# WSC2022SE_TP16_MA2_SPDIF_StartingPoint__.net
KiCad netlist of a schematic drawn in EAGLE
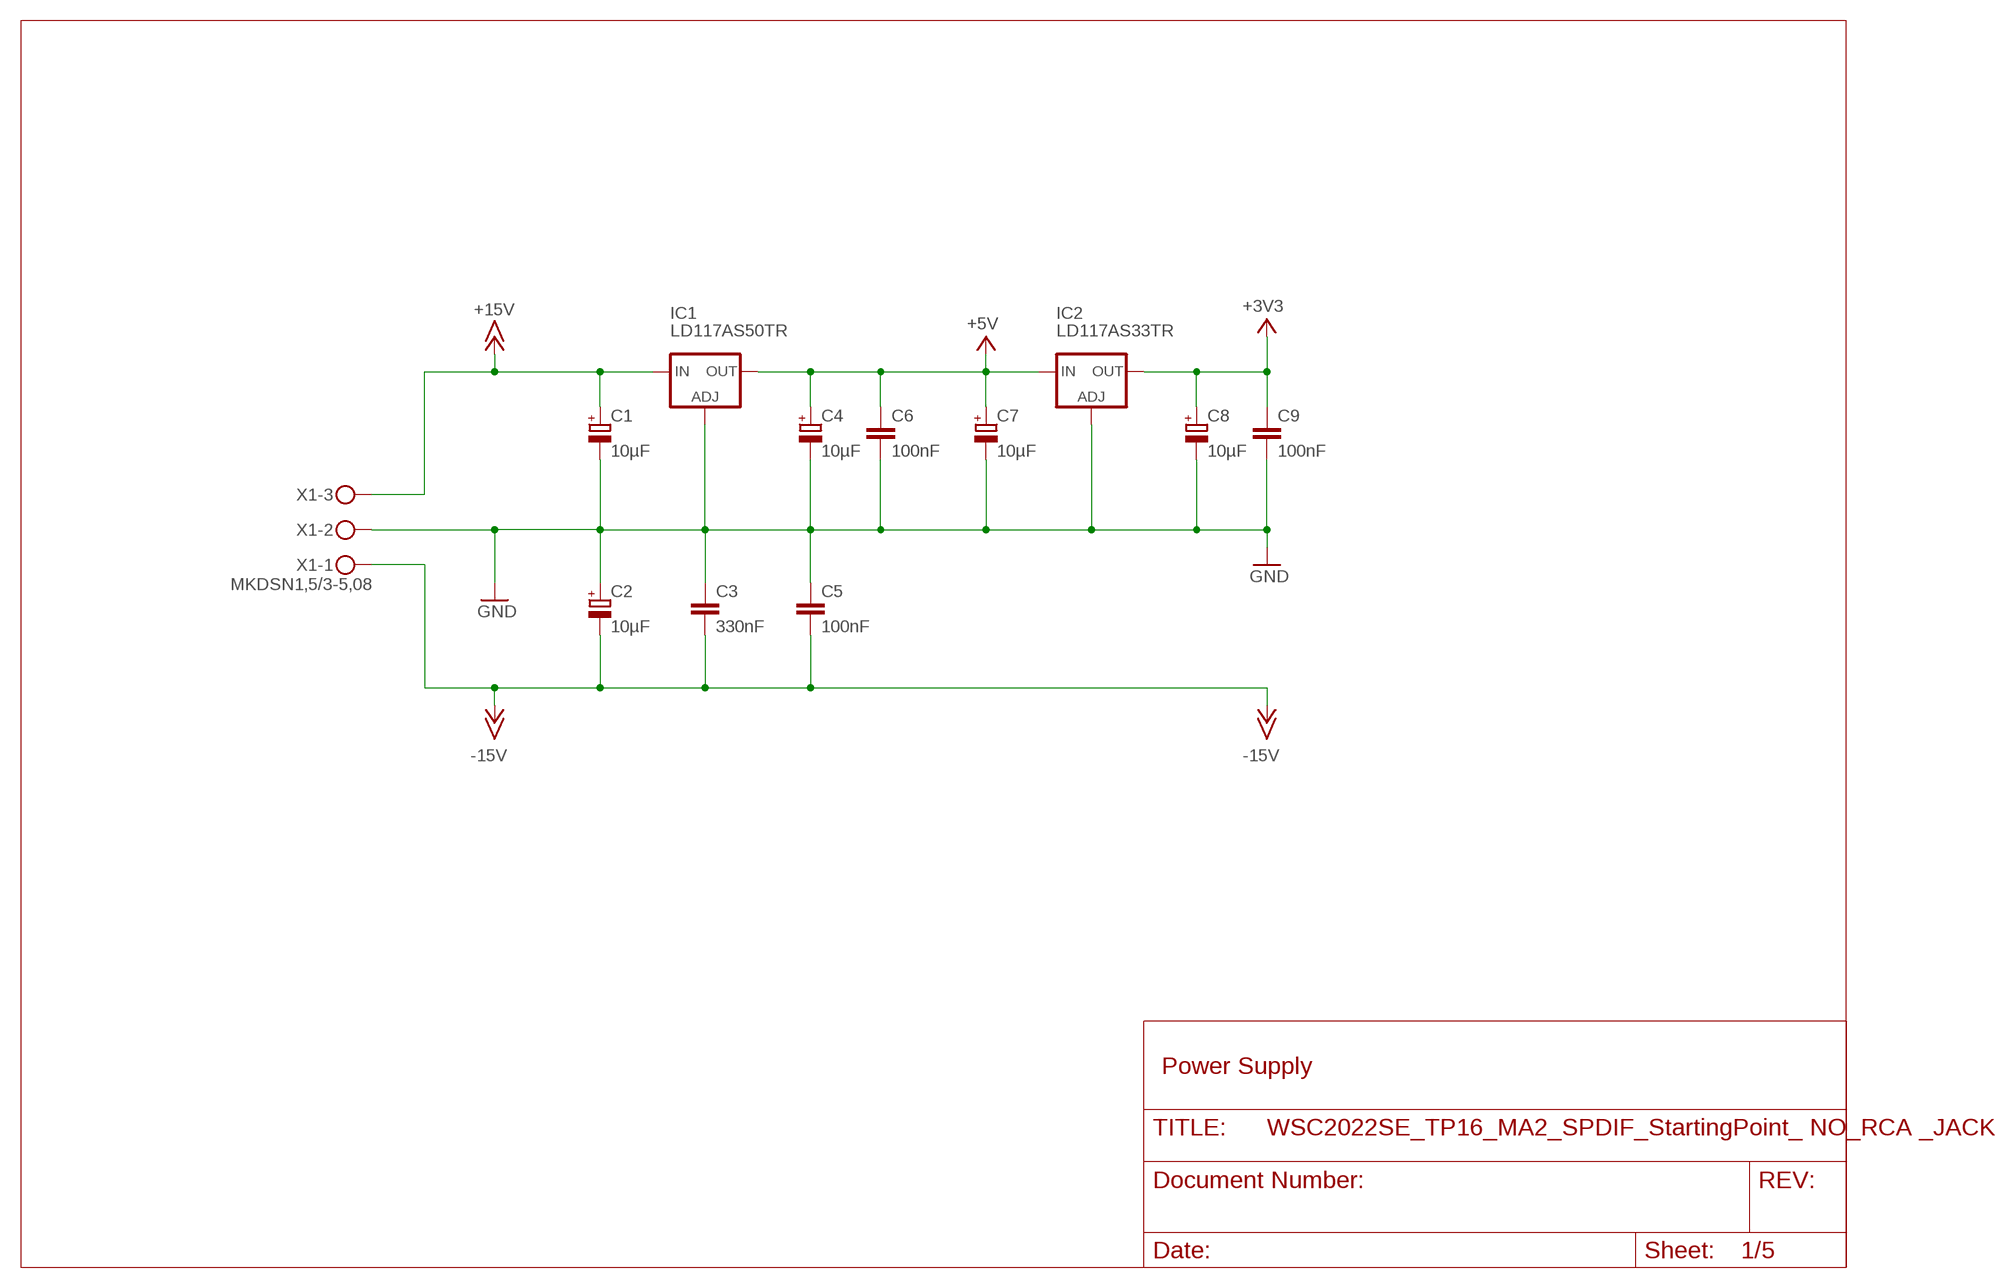
[diagram p0: schematic, sheet 1]
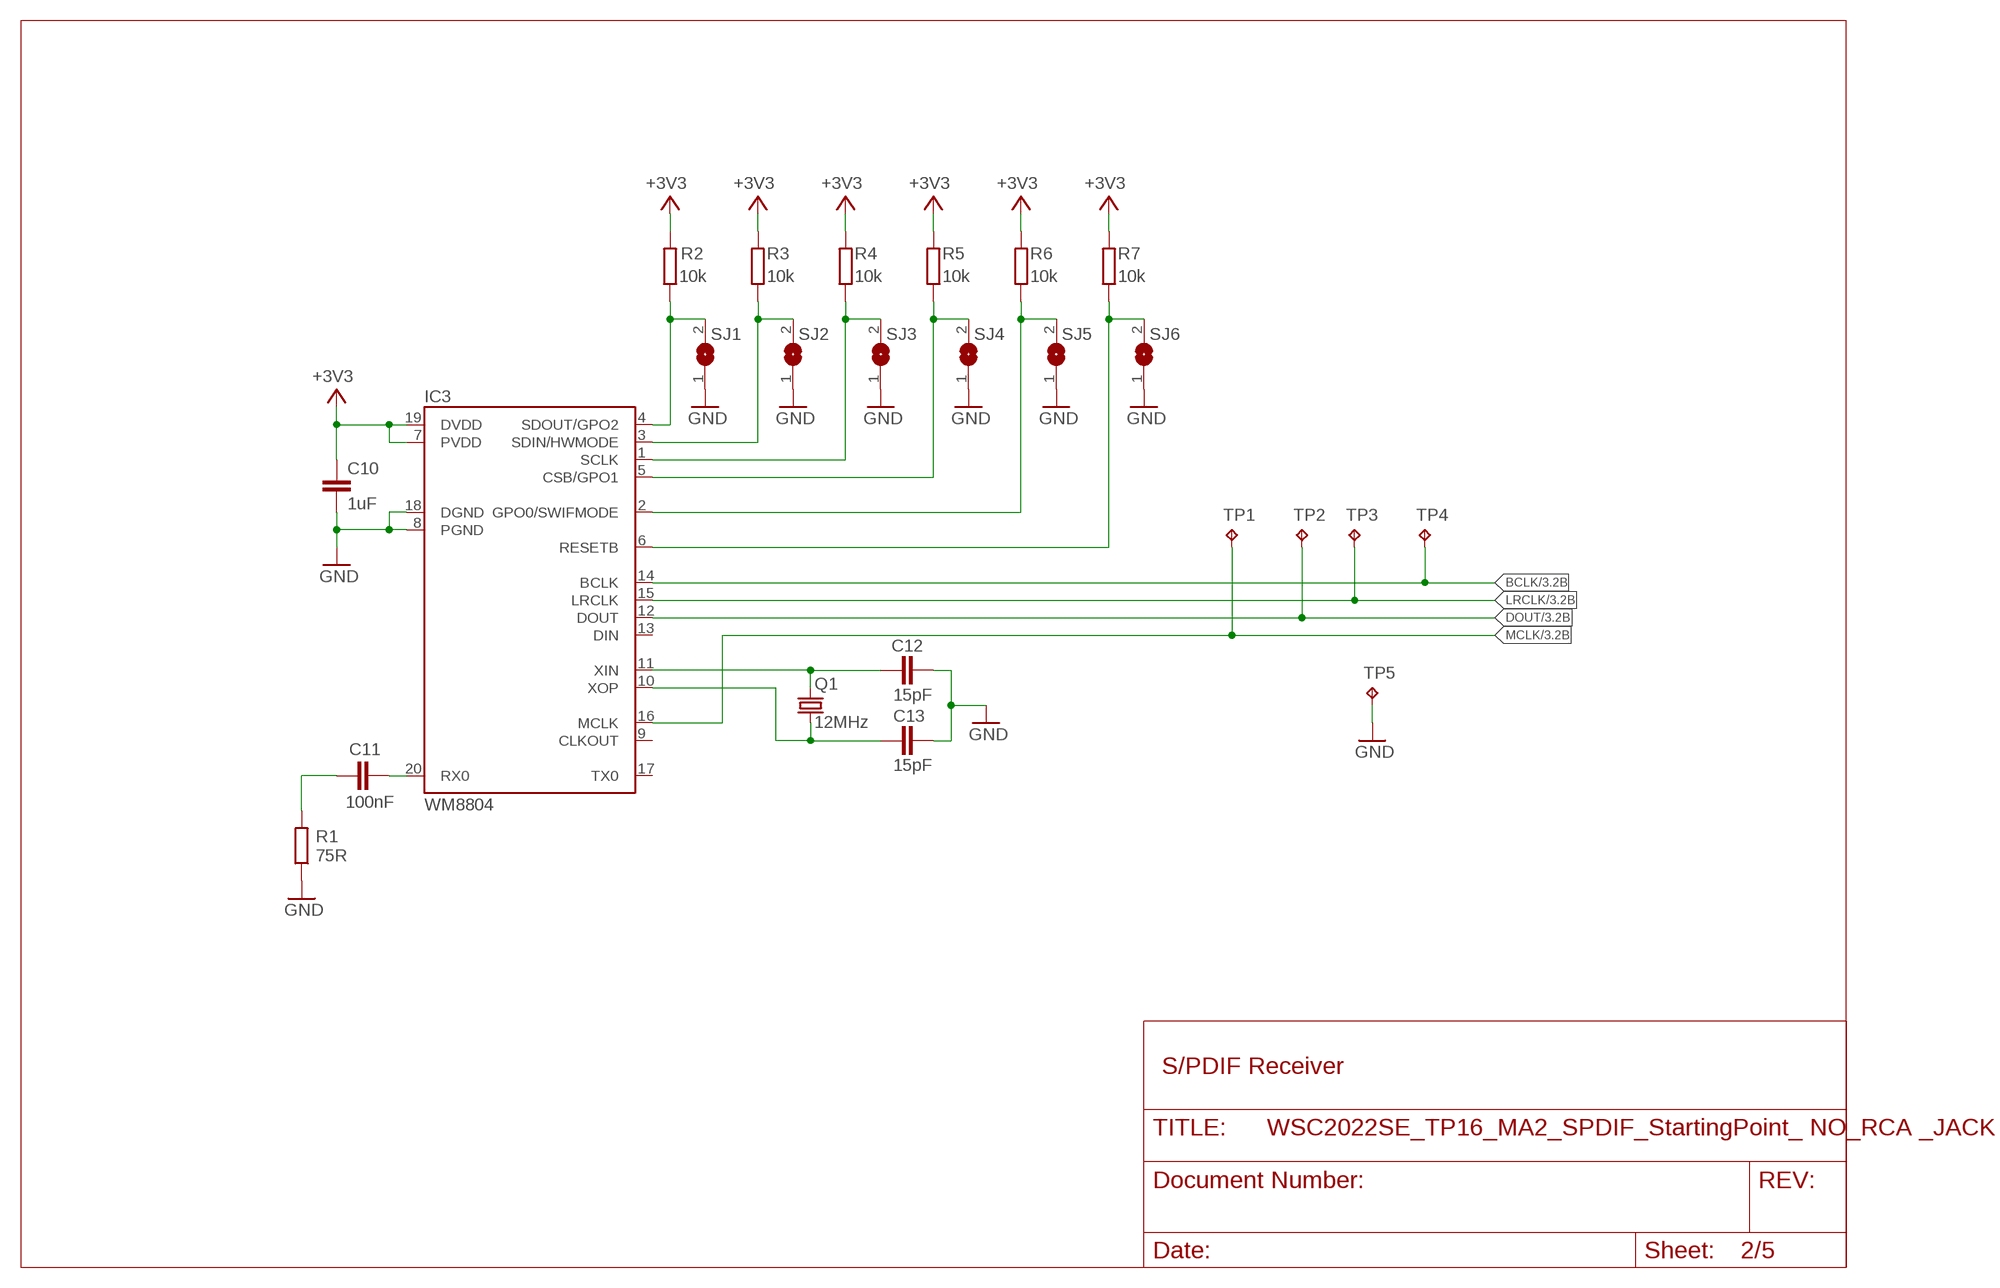
[diagram p1: schematic, sheet 2]
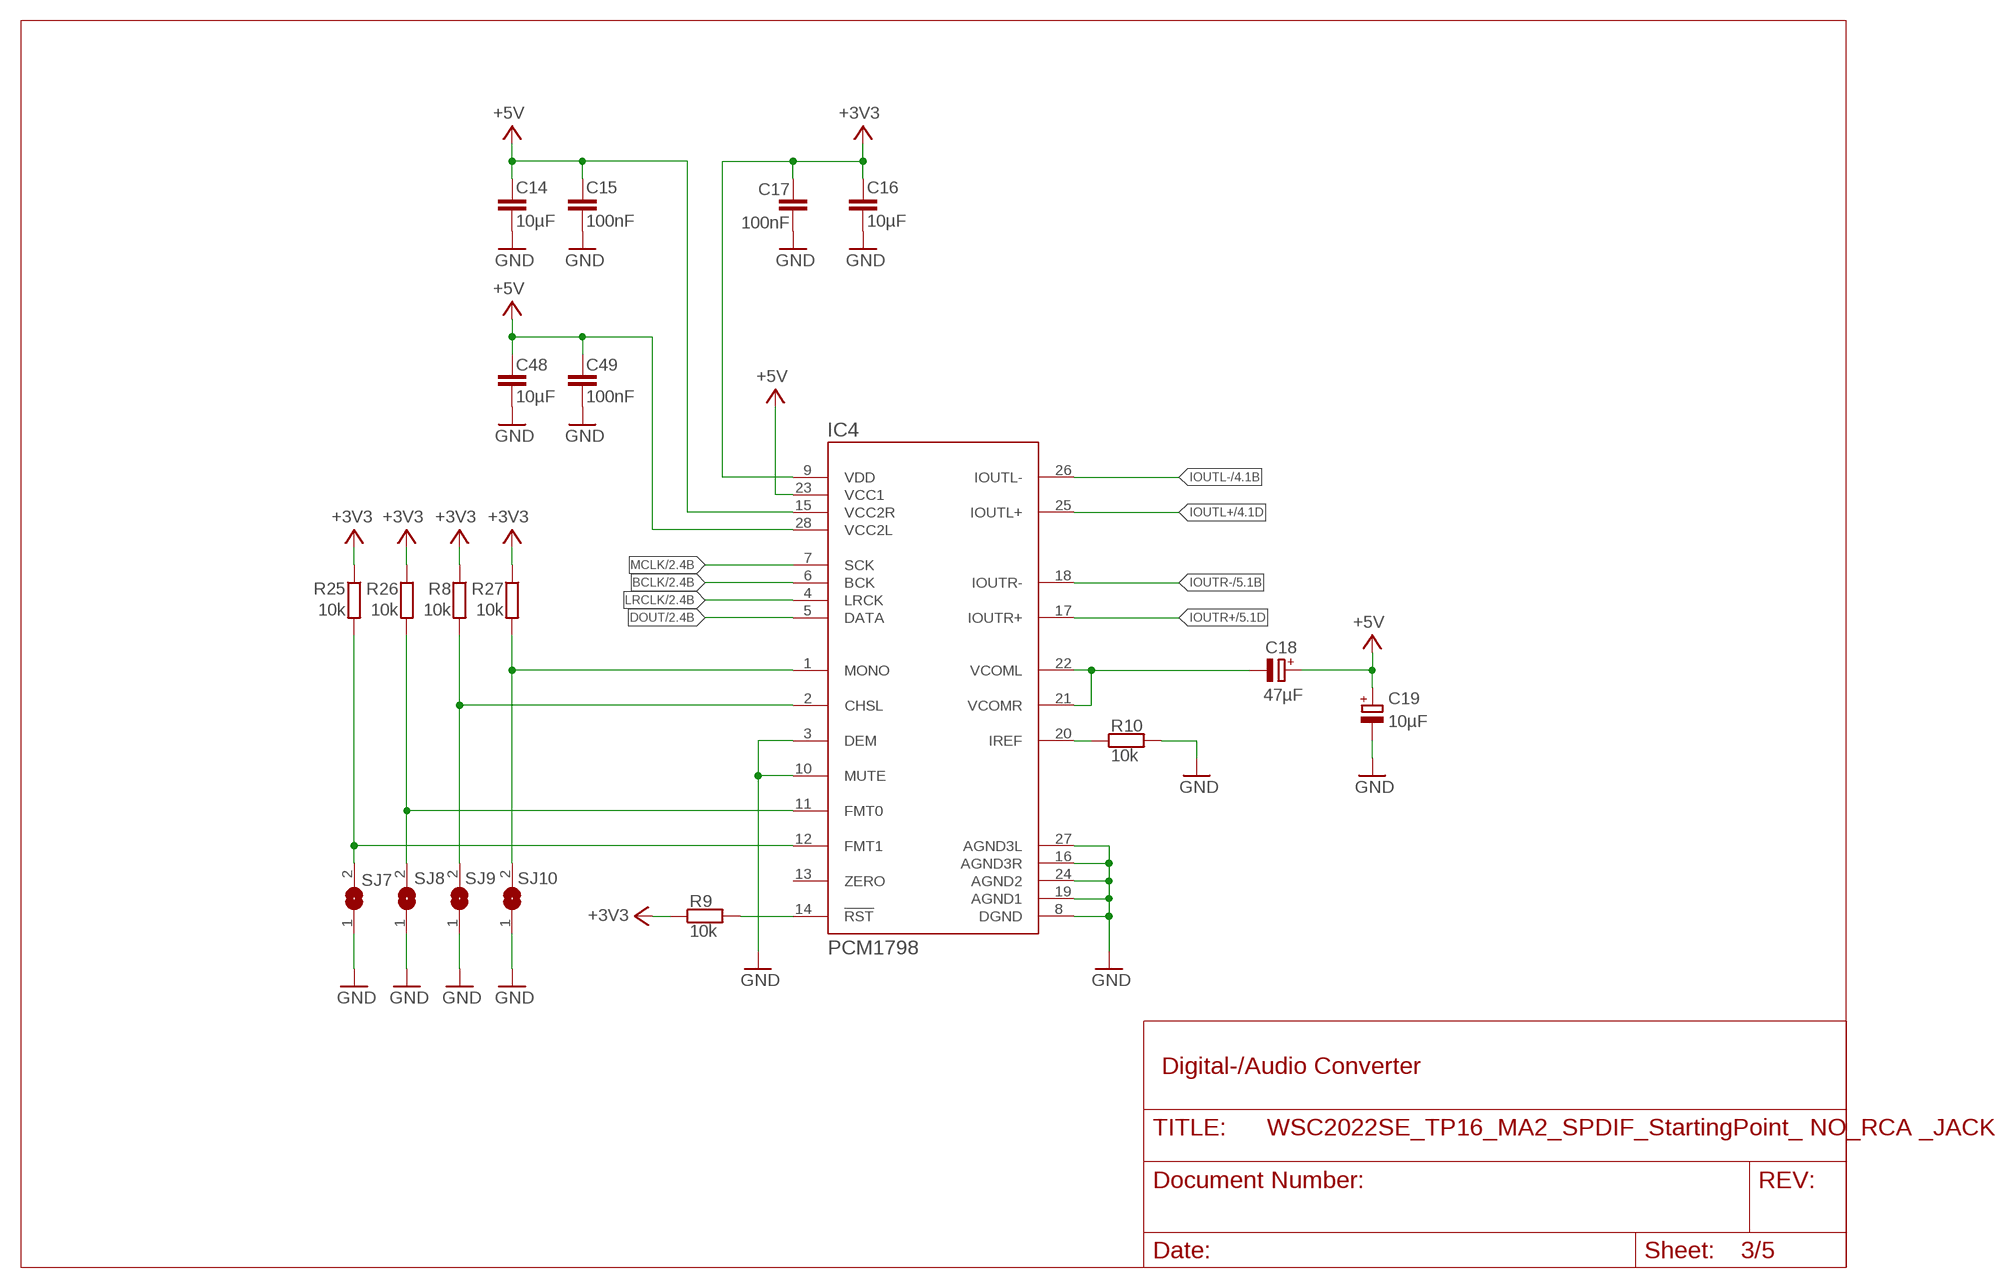
[diagram p2: schematic, sheet 3]
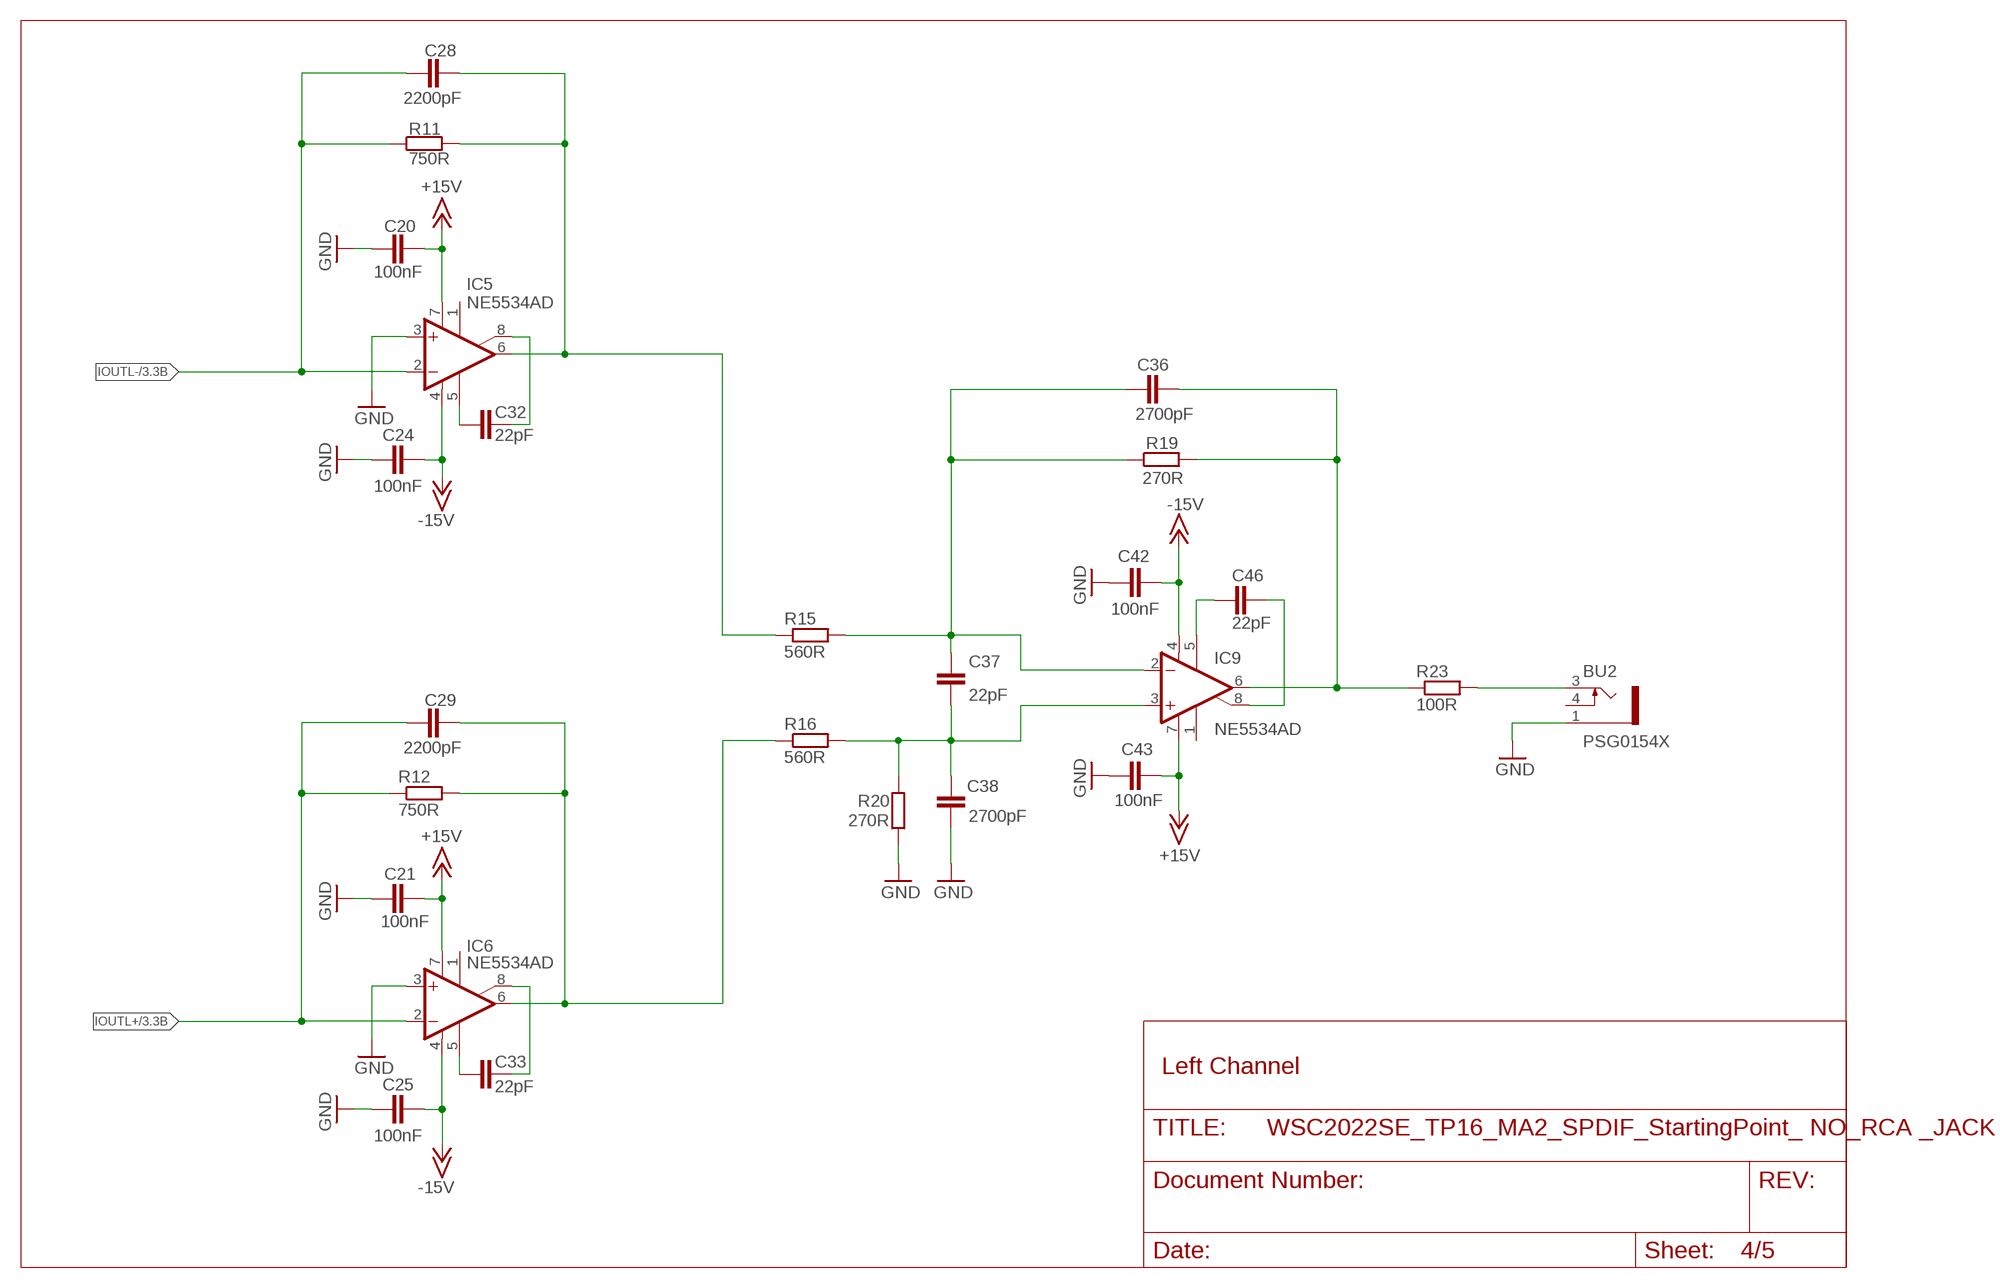
[diagram p3: schematic, sheet 4]
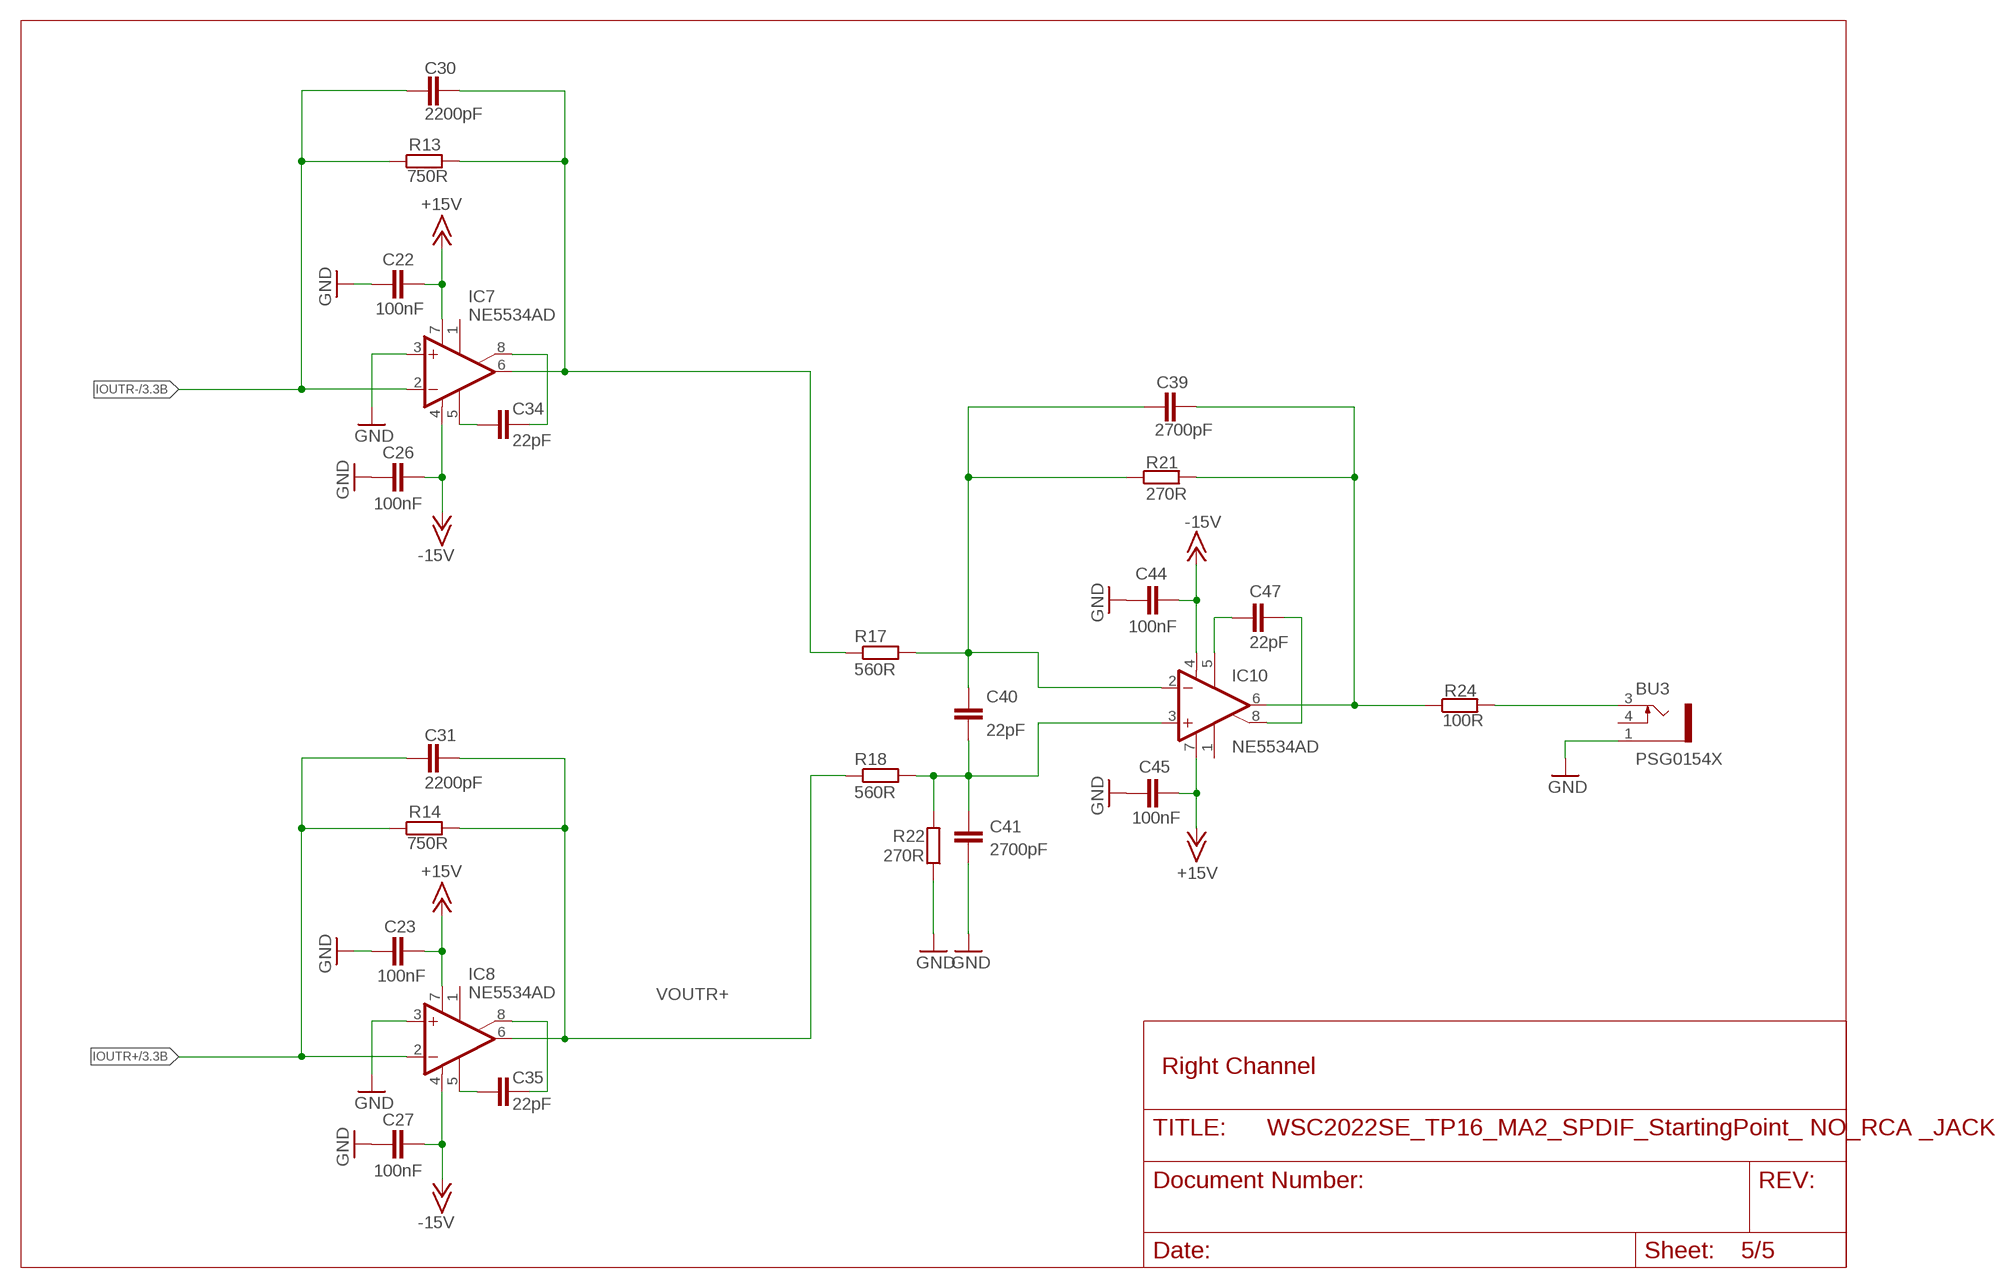
[diagram p4: schematic, sheet 5]

(export (version "E")
  (design (tool "Eeschema 10.0.6"))
  (components
    (comp (ref "BU2")
      (value "PSG0154X")
      (footprint "eagle-import:PHONO-3P")
      (libsource (lib "eagle-import") (part "PSG0154X"))
    )
    (comp (ref "C20")
      (value "100nF")
      (footprint "eagle-import:C0805")
      (libsource (lib "eagle-import") (part "C-EUC0805"))
    )
    (comp (ref "C21")
      (value "100nF")
      (footprint "eagle-import:C0805")
      (libsource (lib "eagle-import") (part "C-EUC0805"))
    )
    (comp (ref "C24")
      (value "100nF")
      (footprint "eagle-import:C0805")
      (libsource (lib "eagle-import") (part "C-EUC0805"))
    )
    (comp (ref "C25")
      (value "100nF")
      (footprint "eagle-import:C0805")
      (libsource (lib "eagle-import") (part "C-EUC0805"))
    )
    (comp (ref "C28")
      (value "2200pF")
      (footprint "eagle-import:C0805")
      (libsource (lib "eagle-import") (part "C-EUC0805"))
    )
    (comp (ref "C29")
      (value "2200pF")
      (footprint "eagle-import:C0805")
      (libsource (lib "eagle-import") (part "C-EUC0805"))
    )
    (comp (ref "C32")
      (value "22pF")
      (footprint "eagle-import:C0805")
      (libsource (lib "eagle-import") (part "C-EUC0805"))
    )
    (comp (ref "C33")
      (value "22pF")
      (footprint "eagle-import:C0805")
      (libsource (lib "eagle-import") (part "C-EUC0805"))
    )
    (comp (ref "C36")
      (value "2700pF")
      (footprint "eagle-import:C0805")
      (libsource (lib "eagle-import") (part "C-EUC0805"))
    )
    (comp (ref "C37")
      (value "22pF")
      (footprint "eagle-import:C0805")
      (libsource (lib "eagle-import") (part "C-EUC0805"))
    )
    (comp (ref "C38")
      (value "2700pF")
      (footprint "eagle-import:C0805")
      (libsource (lib "eagle-import") (part "C-EUC0805"))
    )
    (comp (ref "C42")
      (value "100nF")
      (footprint "eagle-import:C0805")
      (libsource (lib "eagle-import") (part "C-EUC0805"))
    )
    (comp (ref "C43")
      (value "100nF")
      (footprint "eagle-import:C0805")
      (libsource (lib "eagle-import") (part "C-EUC0805"))
    )
    (comp (ref "C46")
      (value "22pF")
      (footprint "eagle-import:C0805")
      (libsource (lib "eagle-import") (part "C-EUC0805"))
    )
    (comp (ref "IC5")
      (value "NE5534AD")
      (footprint "eagle-import:SO08")
      (libsource (lib "eagle-import") (part "NE5534DA"))
    )
    (comp (ref "IC6")
      (value "NE5534AD")
      (footprint "eagle-import:SO08")
      (libsource (lib "eagle-import") (part "NE5534DA"))
    )
    (comp (ref "IC9")
      (value "NE5534AD")
      (footprint "eagle-import:SO08")
      (libsource (lib "eagle-import") (part "NE5534DA"))
    )
    (comp (ref "R11")
      (value "750R")
      (footprint "eagle-import:R0805")
      (libsource (lib "eagle-import") (part "R-EU_R0805"))
    )
    (comp (ref "R12")
      (value "750R")
      (footprint "eagle-import:R0805")
      (libsource (lib "eagle-import") (part "R-EU_R0805"))
    )
    (comp (ref "R15")
      (value "560R")
      (footprint "eagle-import:R0805")
      (libsource (lib "eagle-import") (part "R-EU_R0805"))
    )
    (comp (ref "R16")
      (value "560R")
      (footprint "eagle-import:R0805")
      (libsource (lib "eagle-import") (part "R-EU_R0805"))
    )
    (comp (ref "R19")
      (value "270R")
      (footprint "eagle-import:R0805")
      (libsource (lib "eagle-import") (part "R-EU_R0805"))
    )
    (comp (ref "R20")
      (value "270R")
      (footprint "eagle-import:R0805")
      (libsource (lib "eagle-import") (part "R-EU_R0805"))
    )
    (comp (ref "R23")
      (value "100R")
      (footprint "eagle-import:R0805")
      (libsource (lib "eagle-import") (part "R-EU_R0805"))
    )
    (comp (ref "C14")
      (value "10µF")
      (footprint "eagle-import:C0805")
      (libsource (lib "eagle-import") (part "C-EUC0805"))
    )
    (comp (ref "C15")
      (value "100nF")
      (footprint "eagle-import:C0805")
      (libsource (lib "eagle-import") (part "C-EUC0805"))
    )
    (comp (ref "C16")
      (value "10µF")
      (footprint "eagle-import:C0805")
      (libsource (lib "eagle-import") (part "C-EUC0805"))
    )
    (comp (ref "C17")
      (value "100nF")
      (footprint "eagle-import:C0805")
      (libsource (lib "eagle-import") (part "C-EUC0805"))
    )
    (comp (ref "C18")
      (value "47µF")
      (footprint "eagle-import:PANASONIC_C")
      (libsource (lib "eagle-import") (part "CPOL-EUC"))
    )
    (comp (ref "C19")
      (value "10µF")
      (footprint "eagle-import:PANASONIC_B")
      (libsource (lib "eagle-import") (part "CPOL-EUB"))
    )
    (comp (ref "C48")
      (value "10µF")
      (footprint "eagle-import:C0805")
      (libsource (lib "eagle-import") (part "C-EUC0805"))
    )
    (comp (ref "C49")
      (value "100nF")
      (footprint "eagle-import:C0805")
      (libsource (lib "eagle-import") (part "C-EUC0805"))
    )
    (comp (ref "IC4")
      (value "PCM1798")
      (footprint "eagle-import:SSOP28")
      (libsource (lib "eagle-import") (part "PCM1798"))
    )
    (comp (ref "R8")
      (value "10k")
      (footprint "eagle-import:R0805")
      (libsource (lib "eagle-import") (part "R-EU_R0805"))
    )
    (comp (ref "R9")
      (value "10k")
      (footprint "eagle-import:R0805")
      (libsource (lib "eagle-import") (part "R-EU_R0805"))
    )
    (comp (ref "R10")
      (value "10k")
      (footprint "eagle-import:R0805")
      (libsource (lib "eagle-import") (part "R-EU_R0805"))
    )
    (comp (ref "R25")
      (value "10k")
      (footprint "eagle-import:R0805")
      (libsource (lib "eagle-import") (part "R-EU_R0805"))
    )
    (comp (ref "R26")
      (value "10k")
      (footprint "eagle-import:R0805")
      (libsource (lib "eagle-import") (part "R-EU_R0805"))
    )
    (comp (ref "R27")
      (value "10k")
      (footprint "eagle-import:R0805")
      (libsource (lib "eagle-import") (part "R-EU_R0805"))
    )
    (comp (ref "SJ7") (value "SJ") (footprint "eagle-import:SJ") (libsource (lib "eagle-import") (part "SJ")))
    (comp (ref "SJ8") (value "SJ") (footprint "eagle-import:SJ") (libsource (lib "eagle-import") (part "SJ")))
    (comp (ref "SJ9") (value "SJ") (footprint "eagle-import:SJ") (libsource (lib "eagle-import") (part "SJ")))
    (comp (ref "SJ10")
      (value "SJ")
      (footprint "eagle-import:SJ")
      (libsource (lib "eagle-import") (part "SJ"))
    )
    (comp (ref "BU3")
      (value "PSG0154X")
      (footprint "eagle-import:PHONO-3P")
      (libsource (lib "eagle-import") (part "PSG0154X"))
    )
    (comp (ref "C22")
      (value "100nF")
      (footprint "eagle-import:C0805")
      (libsource (lib "eagle-import") (part "C-EUC0805"))
    )
    (comp (ref "C23")
      (value "100nF")
      (footprint "eagle-import:C0805")
      (libsource (lib "eagle-import") (part "C-EUC0805"))
    )
    (comp (ref "C26")
      (value "100nF")
      (footprint "eagle-import:C0805")
      (libsource (lib "eagle-import") (part "C-EUC0805"))
    )
    (comp (ref "C27")
      (value "100nF")
      (footprint "eagle-import:C0805")
      (libsource (lib "eagle-import") (part "C-EUC0805"))
    )
    (comp (ref "C30")
      (value "2200pF")
      (footprint "eagle-import:C0805")
      (libsource (lib "eagle-import") (part "C-EUC0805"))
    )
    (comp (ref "C31")
      (value "2200pF")
      (footprint "eagle-import:C0805")
      (libsource (lib "eagle-import") (part "C-EUC0805"))
    )
    (comp (ref "C34")
      (value "22pF")
      (footprint "eagle-import:C0805")
      (libsource (lib "eagle-import") (part "C-EUC0805"))
    )
    (comp (ref "C35")
      (value "22pF")
      (footprint "eagle-import:C0805")
      (libsource (lib "eagle-import") (part "C-EUC0805"))
    )
    (comp (ref "C39")
      (value "2700pF")
      (footprint "eagle-import:C0805")
      (libsource (lib "eagle-import") (part "C-EUC0805"))
    )
    (comp (ref "C40")
      (value "22pF")
      (footprint "eagle-import:C0805")
      (libsource (lib "eagle-import") (part "C-EUC0805"))
    )
    (comp (ref "C41")
      (value "2700pF")
      (footprint "eagle-import:C0805")
      (libsource (lib "eagle-import") (part "C-EUC0805"))
    )
    (comp (ref "C44")
      (value "100nF")
      (footprint "eagle-import:C0805")
      (libsource (lib "eagle-import") (part "C-EUC0805"))
    )
    (comp (ref "C45")
      (value "100nF")
      (footprint "eagle-import:C0805")
      (libsource (lib "eagle-import") (part "C-EUC0805"))
    )
    (comp (ref "C47")
      (value "22pF")
      (footprint "eagle-import:C0805")
      (libsource (lib "eagle-import") (part "C-EUC0805"))
    )
    (comp (ref "IC7")
      (value "NE5534AD")
      (footprint "eagle-import:SO08")
      (libsource (lib "eagle-import") (part "NE5534DA"))
    )
    (comp (ref "IC8")
      (value "NE5534AD")
      (footprint "eagle-import:SO08")
      (libsource (lib "eagle-import") (part "NE5534DA"))
    )
    (comp (ref "IC10")
      (value "NE5534AD")
      (footprint "eagle-import:SO08")
      (libsource (lib "eagle-import") (part "NE5534DA"))
    )
    (comp (ref "R13")
      (value "750R")
      (footprint "eagle-import:R0805")
      (libsource (lib "eagle-import") (part "R-EU_R0805"))
    )
    (comp (ref "R14")
      (value "750R")
      (footprint "eagle-import:R0805")
      (libsource (lib "eagle-import") (part "R-EU_R0805"))
    )
    (comp (ref "R17")
      (value "560R")
      (footprint "eagle-import:R0805")
      (libsource (lib "eagle-import") (part "R-EU_R0805"))
    )
    (comp (ref "R18")
      (value "560R")
      (footprint "eagle-import:R0805")
      (libsource (lib "eagle-import") (part "R-EU_R0805"))
    )
    (comp (ref "R21")
      (value "270R")
      (footprint "eagle-import:R0805")
      (libsource (lib "eagle-import") (part "R-EU_R0805"))
    )
    (comp (ref "R22")
      (value "270R")
      (footprint "eagle-import:R0805")
      (libsource (lib "eagle-import") (part "R-EU_R0805"))
    )
    (comp (ref "R24")
      (value "100R")
      (footprint "eagle-import:R0805")
      (libsource (lib "eagle-import") (part "R-EU_R0805"))
    )
    (comp (ref "C1")
      (value "10µF")
      (footprint "eagle-import:CT3528")
      (libsource (lib "eagle-import") (part "CPOL-EUCT3528"))
    )
    (comp (ref "C2")
      (value "10µF")
      (footprint "eagle-import:CT3528")
      (libsource (lib "eagle-import") (part "CPOL-EUCT3528"))
    )
    (comp (ref "C3")
      (value "330nF")
      (footprint "eagle-import:C0805")
      (libsource (lib "eagle-import") (part "C-EUC0805"))
    )
    (comp (ref "C4")
      (value "10µF")
      (footprint "eagle-import:CT3528")
      (libsource (lib "eagle-import") (part "CPOL-EUCT3528"))
    )
    (comp (ref "C5")
      (value "100nF")
      (footprint "eagle-import:C0805")
      (libsource (lib "eagle-import") (part "C-EUC0805"))
    )
    (comp (ref "C6")
      (value "100nF")
      (footprint "eagle-import:C0805")
      (libsource (lib "eagle-import") (part "C-EUC0805"))
    )
    (comp (ref "C7")
      (value "10µF")
      (footprint "eagle-import:CT3528")
      (libsource (lib "eagle-import") (part "CPOL-EUCT3528"))
    )
    (comp (ref "C8")
      (value "10µF")
      (footprint "eagle-import:CT3528")
      (libsource (lib "eagle-import") (part "CPOL-EUCT3528"))
    )
    (comp (ref "C9")
      (value "100nF")
      (footprint "eagle-import:C0805")
      (libsource (lib "eagle-import") (part "C-EUC0805"))
    )
    (comp (ref "IC1")
      (value "LD117AS50TR")
      (footprint "eagle-import:SOT223")
      (libsource (lib "eagle-import") (part "LD117A?S50TR"))
    )
    (comp (ref "IC2")
      (value "LD117AS33TR")
      (footprint "eagle-import:SOT223")
      (libsource (lib "eagle-import") (part "LD117A?S50TR"))
    )
    (comp (ref "X1")
      (value "MKDSN1,5/3-5,08")
      (footprint "eagle-import:MKDSN1,5_3-5,08")
      (libsource (lib "eagle-import") (part "MKDSN1,5/3-5,08"))
    )
    (comp (ref "C10")
      (value "1uF")
      (footprint "eagle-import:C0805")
      (libsource (lib "eagle-import") (part "C-EUC0805"))
    )
    (comp (ref "C11")
      (value "100nF")
      (footprint "eagle-import:C0805")
      (libsource (lib "eagle-import") (part "C-EUC0805"))
    )
    (comp (ref "C12")
      (value "15pF")
      (footprint "eagle-import:C0805")
      (libsource (lib "eagle-import") (part "C-EUC0805"))
    )
    (comp (ref "C13")
      (value "15pF")
      (footprint "eagle-import:C0805")
      (libsource (lib "eagle-import") (part "C-EUC0805"))
    )
    (comp (ref "IC3")
      (value "WM8804")
      (footprint "eagle-import:SSOP20BU")
      (libsource (lib "eagle-import") (part "WM8804BU"))
    )
    (comp (ref "Q1")
      (value "12MHz")
      (footprint "eagle-import:5.0X3.2_2")
      (libsource (lib "eagle-import") (part "KX-9B"))
    )
    (comp (ref "R1")
      (value "75R")
      (footprint "eagle-import:R0805")
      (libsource (lib "eagle-import") (part "R-EU_R0805"))
    )
    (comp (ref "R2")
      (value "10k")
      (footprint "eagle-import:R0805")
      (libsource (lib "eagle-import") (part "R-EU_R0805"))
    )
    (comp (ref "R3")
      (value "10k")
      (footprint "eagle-import:R0805")
      (libsource (lib "eagle-import") (part "R-EU_R0805"))
    )
    (comp (ref "R4")
      (value "10k")
      (footprint "eagle-import:R0805")
      (libsource (lib "eagle-import") (part "R-EU_R0805"))
    )
    (comp (ref "R5")
      (value "10k")
      (footprint "eagle-import:R0805")
      (libsource (lib "eagle-import") (part "R-EU_R0805"))
    )
    (comp (ref "R6")
      (value "10k")
      (footprint "eagle-import:R0805")
      (libsource (lib "eagle-import") (part "R-EU_R0805"))
    )
    (comp (ref "R7")
      (value "10k")
      (footprint "eagle-import:R0805")
      (libsource (lib "eagle-import") (part "R-EU_R0805"))
    )
    (comp (ref "SJ1") (value "SJ") (footprint "eagle-import:SJ") (libsource (lib "eagle-import") (part "SJ")))
    (comp (ref "SJ2") (value "SJ") (footprint "eagle-import:SJ") (libsource (lib "eagle-import") (part "SJ")))
    (comp (ref "SJ3") (value "SJ") (footprint "eagle-import:SJ") (libsource (lib "eagle-import") (part "SJ")))
    (comp (ref "SJ4") (value "SJ") (footprint "eagle-import:SJ") (libsource (lib "eagle-import") (part "SJ")))
    (comp (ref "SJ5") (value "SJ") (footprint "eagle-import:SJ") (libsource (lib "eagle-import") (part "SJ")))
    (comp (ref "SJ6") (value "SJ") (footprint "eagle-import:SJ") (libsource (lib "eagle-import") (part "SJ")))
    (comp (ref "TP1")
      (value "TPB2,54")
      (footprint "eagle-import:B2,54")
      (libsource (lib "eagle-import") (part "TPB2,54"))
    )
    (comp (ref "TP2")
      (value "TPB2,54")
      (footprint "eagle-import:B2,54")
      (libsource (lib "eagle-import") (part "TPB2,54"))
    )
    (comp (ref "TP3")
      (value "TPB2,54")
      (footprint "eagle-import:B2,54")
      (libsource (lib "eagle-import") (part "TPB2,54"))
    )
    (comp (ref "TP4")
      (value "TPB2,54")
      (footprint "eagle-import:B2,54")
      (libsource (lib "eagle-import") (part "TPB2,54"))
    )
    (comp (ref "TP5")
      (value "TPB2,54")
      (footprint "eagle-import:B2,54")
      (libsource (lib "eagle-import") (part "TPB2,54"))
    )
  )
  (nets
    (net (code "1") (name "+3V3") (class "Default")
      (node (ref "C10") (pin "1") (pinfunction "1_1") (pintype "passive"))
      (node (ref "C16") (pin "2") (pinfunction "2_2") (pintype "passive"))
      (node (ref "C17") (pin "2") (pinfunction "2_2") (pintype "passive"))
      (node (ref "C8") (pin "+") (pinfunction "+_+") (pintype "passive"))
      (node (ref "C9") (pin "1") (pinfunction "1_1") (pintype "passive"))
      (node (ref "IC2") (pin "2") (pinfunction "OUT_2") (pintype "passive"))
      (node (ref "IC2") (pin "4") (pinfunction "OUT_4") (pintype "passive"))
      (node (ref "IC3") (pin "19") (pinfunction "DVDD_19") (pintype "power_in"))
      (node (ref "IC3") (pin "7") (pinfunction "PVDD_7") (pintype "power_in"))
      (node (ref "IC4") (pin "9") (pinfunction "VDD_9") (pintype "power_in"))
      (node (ref "R2") (pin "2") (pinfunction "2_2") (pintype "passive"))
      (node (ref "R25") (pin "1") (pinfunction "1_1") (pintype "passive"))
      (node (ref "R26") (pin "1") (pinfunction "1_1") (pintype "passive"))
      (node (ref "R27") (pin "1") (pinfunction "1_1") (pintype "passive"))
      (node (ref "R3") (pin "2") (pinfunction "2_2") (pintype "passive"))
      (node (ref "R4") (pin "2") (pinfunction "2_2") (pintype "passive"))
      (node (ref "R5") (pin "2") (pinfunction "2_2") (pintype "passive"))
      (node (ref "R6") (pin "2") (pinfunction "2_2") (pintype "passive"))
      (node (ref "R7") (pin "2") (pinfunction "2_2") (pintype "passive"))
      (node (ref "R8") (pin "1") (pinfunction "1_1") (pintype "passive"))
      (node (ref "R9") (pin "1") (pinfunction "1_1") (pintype "passive"))
    )
    (net (code "2") (name "+5V") (class "Default")
      (node (ref "C14") (pin "1") (pinfunction "1_1") (pintype "passive"))
      (node (ref "C15") (pin "1") (pinfunction "1_1") (pintype "passive"))
      (node (ref "C18") (pin "+") (pinfunction "+_+") (pintype "passive"))
      (node (ref "C19") (pin "+") (pinfunction "+_+") (pintype "passive"))
      (node (ref "C4") (pin "+") (pinfunction "+_+") (pintype "passive"))
      (node (ref "C48") (pin "1") (pinfunction "1_1") (pintype "passive"))
      (node (ref "C49") (pin "1") (pinfunction "1_1") (pintype "passive"))
      (node (ref "C6") (pin "1") (pinfunction "1_1") (pintype "passive"))
      (node (ref "C7") (pin "+") (pinfunction "+_+") (pintype "passive"))
      (node (ref "IC1") (pin "2") (pinfunction "OUT_2") (pintype "passive"))
      (node (ref "IC1") (pin "4") (pinfunction "OUT_4") (pintype "passive"))
      (node (ref "IC2") (pin "3") (pinfunction "IN_3") (pintype "input"))
      (node (ref "IC4") (pin "15") (pinfunction "VCC2R_15") (pintype "power_in"))
      (node (ref "IC4") (pin "23") (pinfunction "VCC1_23") (pintype "power_in"))
      (node (ref "IC4") (pin "28") (pinfunction "VCC2L_28") (pintype "power_in"))
    )
    (net (code "3") (name "+15V") (class "Default")
      (node (ref "C1") (pin "+") (pinfunction "+_+") (pintype "passive"))
      (node (ref "C20") (pin "1") (pinfunction "1_1") (pintype "passive"))
      (node (ref "C21") (pin "1") (pinfunction "1_1") (pintype "passive"))
      (node (ref "C22") (pin "1") (pinfunction "1_1") (pintype "passive"))
      (node (ref "C23") (pin "1") (pinfunction "1_1") (pintype "passive"))
      (node (ref "C43") (pin "1") (pinfunction "1_1") (pintype "passive"))
      (node (ref "C45") (pin "1") (pinfunction "1_1") (pintype "passive"))
      (node (ref "IC1") (pin "3") (pinfunction "IN_3") (pintype "input"))
      (node (ref "IC10") (pin "7") (pinfunction "V+_7") (pintype "power_in"))
      (node (ref "IC5") (pin "7") (pinfunction "V+_7") (pintype "power_in"))
      (node (ref "IC6") (pin "7") (pinfunction "V+_7") (pintype "power_in"))
      (node (ref "IC7") (pin "7") (pinfunction "V+_7") (pintype "power_in"))
      (node (ref "IC8") (pin "7") (pinfunction "V+_7") (pintype "power_in"))
      (node (ref "IC9") (pin "7") (pinfunction "V+_7") (pintype "power_in"))
      (node (ref "X1") (pin "3") (pinfunction "KL_3") (pintype "passive"))
    )
    (net (code "4") (name "-15V") (class "Default")
      (node (ref "C2") (pin "-") (pinfunction "-_-") (pintype "passive"))
      (node (ref "C24") (pin "1") (pinfunction "1_1") (pintype "passive"))
      (node (ref "C25") (pin "1") (pinfunction "1_1") (pintype "passive"))
      (node (ref "C26") (pin "1") (pinfunction "1_1") (pintype "passive"))
      (node (ref "C27") (pin "1") (pinfunction "1_1") (pintype "passive"))
      (node (ref "C3") (pin "2") (pinfunction "2_2") (pintype "passive"))
      (node (ref "C42") (pin "1") (pinfunction "1_1") (pintype "passive"))
      (node (ref "C44") (pin "1") (pinfunction "1_1") (pintype "passive"))
      (node (ref "C5") (pin "2") (pinfunction "2_2") (pintype "passive"))
      (node (ref "IC10") (pin "4") (pinfunction "V-_4") (pintype "power_in"))
      (node (ref "IC5") (pin "4") (pinfunction "V-_4") (pintype "power_in"))
      (node (ref "IC6") (pin "4") (pinfunction "V-_4") (pintype "power_in"))
      (node (ref "IC7") (pin "4") (pinfunction "V-_4") (pintype "power_in"))
      (node (ref "IC8") (pin "4") (pinfunction "V-_4") (pintype "power_in"))
      (node (ref "IC9") (pin "4") (pinfunction "V-_4") (pintype "power_in"))
      (node (ref "X1") (pin "1") (pinfunction "KL_1") (pintype "passive"))
    )
    (net (code "5") (name "BCLK") (class "Default")
      (node (ref "IC3") (pin "14") (pinfunction "BCLK_14") (pintype "output"))
      (node (ref "IC4") (pin "6") (pinfunction "BCK_6") (pintype "input"))
      (node (ref "TP4") (pin "TP") (pinfunction "TP_TP") (pintype "input"))
    )
    (net (code "6") (name "DOUT") (class "Default")
      (node (ref "IC3") (pin "12") (pinfunction "DOUT_12") (pintype "output"))
      (node (ref "IC4") (pin "5") (pinfunction "DATA_5") (pintype "input"))
      (node (ref "TP2") (pin "TP") (pinfunction "TP_TP") (pintype "input"))
    )
    (net (code "7") (name "GND") (class "Default")
      (node (ref "BU2") (pin "1") (pinfunction "1_1") (pintype "passive"))
      (node (ref "BU3") (pin "1") (pinfunction "1_1") (pintype "passive"))
      (node (ref "C1") (pin "-") (pinfunction "-_-") (pintype "passive"))
      (node (ref "C10") (pin "2") (pinfunction "2_2") (pintype "passive"))
      (node (ref "C12") (pin "1") (pinfunction "1_1") (pintype "passive"))
      (node (ref "C13") (pin "1") (pinfunction "1_1") (pintype "passive"))
      (node (ref "C14") (pin "2") (pinfunction "2_2") (pintype "passive"))
      (node (ref "C15") (pin "2") (pinfunction "2_2") (pintype "passive"))
      (node (ref "C16") (pin "1") (pinfunction "1_1") (pintype "passive"))
      (node (ref "C17") (pin "1") (pinfunction "1_1") (pintype "passive"))
      (node (ref "C19") (pin "-") (pinfunction "-_-") (pintype "passive"))
      (node (ref "C2") (pin "+") (pinfunction "+_+") (pintype "passive"))
      (node (ref "C20") (pin "2") (pinfunction "2_2") (pintype "passive"))
      (node (ref "C21") (pin "2") (pinfunction "2_2") (pintype "passive"))
      (node (ref "C22") (pin "2") (pinfunction "2_2") (pintype "passive"))
      (node (ref "C23") (pin "2") (pinfunction "2_2") (pintype "passive"))
      (node (ref "C24") (pin "2") (pinfunction "2_2") (pintype "passive"))
      (node (ref "C25") (pin "2") (pinfunction "2_2") (pintype "passive"))
      (node (ref "C26") (pin "2") (pinfunction "2_2") (pintype "passive"))
      (node (ref "C27") (pin "2") (pinfunction "2_2") (pintype "passive"))
      (node (ref "C3") (pin "1") (pinfunction "1_1") (pintype "passive"))
      (node (ref "C38") (pin "2") (pinfunction "2_2") (pintype "passive"))
      (node (ref "C4") (pin "-") (pinfunction "-_-") (pintype "passive"))
      (node (ref "C41") (pin "2") (pinfunction "2_2") (pintype "passive"))
      (node (ref "C42") (pin "2") (pinfunction "2_2") (pintype "passive"))
      (node (ref "C43") (pin "2") (pinfunction "2_2") (pintype "passive"))
      (node (ref "C44") (pin "2") (pinfunction "2_2") (pintype "passive"))
      (node (ref "C45") (pin "2") (pinfunction "2_2") (pintype "passive"))
      (node (ref "C48") (pin "2") (pinfunction "2_2") (pintype "passive"))
      (node (ref "C49") (pin "2") (pinfunction "2_2") (pintype "passive"))
      (node (ref "C5") (pin "1") (pinfunction "1_1") (pintype "passive"))
      (node (ref "C6") (pin "2") (pinfunction "2_2") (pintype "passive"))
      (node (ref "C7") (pin "-") (pinfunction "-_-") (pintype "passive"))
      (node (ref "C8") (pin "-") (pinfunction "-_-") (pintype "passive"))
      (node (ref "C9") (pin "2") (pinfunction "2_2") (pintype "passive"))
      (node (ref "IC1") (pin "1") (pinfunction "ADJ_1") (pintype "input"))
      (node (ref "IC2") (pin "1") (pinfunction "ADJ_1") (pintype "input"))
      (node (ref "IC3") (pin "18") (pinfunction "DGND_18") (pintype "power_in"))
      (node (ref "IC3") (pin "8") (pinfunction "PGND_8") (pintype "power_in"))
      (node (ref "IC4") (pin "10") (pinfunction "MUTE_10") (pintype "bidirectional"))
      (node (ref "IC4") (pin "16") (pinfunction "AGND3R_16") (pintype "power_in"))
      (node (ref "IC4") (pin "19") (pinfunction "AGND1_19") (pintype "power_in"))
      (node (ref "IC4") (pin "24") (pinfunction "AGND2_24") (pintype "power_in"))
      (node (ref "IC4") (pin "27") (pinfunction "AGND3L_27") (pintype "power_in"))
      (node (ref "IC4") (pin "3") (pinfunction "DEM_3") (pintype "input"))
      (node (ref "IC4") (pin "8") (pinfunction "DGND_8") (pintype "power_in"))
      (node (ref "IC5") (pin "3") (pinfunction "+IN_3") (pintype "input"))
      (node (ref "IC6") (pin "3") (pinfunction "+IN_3") (pintype "input"))
      (node (ref "IC7") (pin "3") (pinfunction "+IN_3") (pintype "input"))
      (node (ref "IC8") (pin "3") (pinfunction "+IN_3") (pintype "input"))
      (node (ref "R1") (pin "1") (pinfunction "1_1") (pintype "passive"))
      (node (ref "R10") (pin "2") (pinfunction "2_2") (pintype "passive"))
      (node (ref "R20") (pin "1") (pinfunction "1_1") (pintype "passive"))
      (node (ref "R22") (pin "1") (pinfunction "1_1") (pintype "passive"))
      (node (ref "SJ1") (pin "1") (pinfunction "1_1") (pintype "passive"))
      (node (ref "SJ10") (pin "1") (pinfunction "1_1") (pintype "passive"))
      (node (ref "SJ2") (pin "1") (pinfunction "1_1") (pintype "passive"))
      (node (ref "SJ3") (pin "1") (pinfunction "1_1") (pintype "passive"))
      (node (ref "SJ4") (pin "1") (pinfunction "1_1") (pintype "passive"))
      (node (ref "SJ5") (pin "1") (pinfunction "1_1") (pintype "passive"))
      (node (ref "SJ6") (pin "1") (pinfunction "1_1") (pintype "passive"))
      (node (ref "SJ7") (pin "1") (pinfunction "1_1") (pintype "passive"))
      (node (ref "SJ8") (pin "1") (pinfunction "1_1") (pintype "passive"))
      (node (ref "SJ9") (pin "1") (pinfunction "1_1") (pintype "passive"))
      (node (ref "TP5") (pin "TP") (pinfunction "TP_TP") (pintype "input"))
      (node (ref "X1") (pin "2") (pinfunction "KL_2") (pintype "passive"))
    )
    (net (code "8") (name "IOUTL+") (class "Default")
      (node (ref "C29") (pin "1") (pinfunction "1_1") (pintype "passive"))
      (node (ref "IC4") (pin "25") (pinfunction "IOUTL+_25") (pintype "output"))
      (node (ref "IC6") (pin "2") (pinfunction "-IN_2") (pintype "input"))
      (node (ref "R12") (pin "1") (pinfunction "1_1") (pintype "passive"))
    )
    (net (code "9") (name "IOUTL-") (class "Default")
      (node (ref "C28") (pin "1") (pinfunction "1_1") (pintype "passive"))
      (node (ref "IC4") (pin "26") (pinfunction "IOUTL-_26") (pintype "output"))
      (node (ref "IC5") (pin "2") (pinfunction "-IN_2") (pintype "input"))
      (node (ref "R11") (pin "1") (pinfunction "1_1") (pintype "passive"))
    )
    (net (code "10") (name "IOUTR+") (class "Default")
      (node (ref "C31") (pin "1") (pinfunction "1_1") (pintype "passive"))
      (node (ref "IC4") (pin "17") (pinfunction "IOUTR+_17") (pintype "output"))
      (node (ref "IC8") (pin "2") (pinfunction "-IN_2") (pintype "input"))
      (node (ref "R14") (pin "1") (pinfunction "1_1") (pintype "passive"))
    )
    (net (code "11") (name "IOUTR-") (class "Default")
      (node (ref "C30") (pin "1") (pinfunction "1_1") (pintype "passive"))
      (node (ref "IC4") (pin "18") (pinfunction "IOUTR-_18") (pintype "output"))
      (node (ref "IC7") (pin "2") (pinfunction "-IN_2") (pintype "input"))
      (node (ref "R13") (pin "1") (pinfunction "1_1") (pintype "passive"))
    )
    (net (code "12") (name "LRCLK") (class "Default")
      (node (ref "IC3") (pin "15") (pinfunction "LRCLK_15") (pintype "output"))
      (node (ref "IC4") (pin "4") (pinfunction "LRCK_4") (pintype "input"))
      (node (ref "TP3") (pin "TP") (pinfunction "TP_TP") (pintype "input"))
    )
    (net (code "13") (name "MCLK") (class "Default")
      (node (ref "IC3") (pin "16") (pinfunction "MCLK_16") (pintype "bidirectional"))
      (node (ref "IC4") (pin "7") (pinfunction "SCK_7") (pintype "input"))
      (node (ref "TP1") (pin "TP") (pinfunction "TP_TP") (pintype "input"))
    )
    (net (code "14") (name "Net-(BU2-Pad3)") (class "Default")
      (node (ref "BU2") (pin "3") (pinfunction "3_3") (pintype "passive"))
      (node (ref "R23") (pin "2") (pinfunction "2_2") (pintype "passive"))
    )
    (net (code "15") (name "Net-(BU3-Pad3)") (class "Default")
      (node (ref "BU3") (pin "3") (pinfunction "3_3") (pintype "passive"))
      (node (ref "R24") (pin "2") (pinfunction "2_2") (pintype "passive"))
    )
    (net (code "16") (name "Net-(C11-Pad1)") (class "Default")
      (node (ref "C11") (pin "1") (pinfunction "1_1") (pintype "passive"))
      (node (ref "R1") (pin "2") (pinfunction "2_2") (pintype "passive"))
    )
    (net (code "17") (name "Net-(IC3-CSB{slash}GPO1)") (class "Default")
      (node (ref "IC3") (pin "5") (pinfunction "CSB/GPO1_5") (pintype "output"))
      (node (ref "R5") (pin "1") (pinfunction "1_1") (pintype "passive"))
      (node (ref "SJ4") (pin "2") (pinfunction "2_2") (pintype "passive"))
    )
    (net (code "18") (name "Net-(IC3-GPO0{slash}SWIFMODE)") (class "Default")
      (node (ref "IC3") (pin "2") (pinfunction "GPO0/SWIFMODE_2") (pintype "input"))
      (node (ref "R6") (pin "1") (pinfunction "1_1") (pintype "passive"))
      (node (ref "SJ5") (pin "2") (pinfunction "2_2") (pintype "passive"))
    )
    (net (code "19") (name "Net-(IC3-RESETB)") (class "Default")
      (node (ref "IC3") (pin "6") (pinfunction "RESETB_6") (pintype "bidirectional"))
      (node (ref "R7") (pin "1") (pinfunction "1_1") (pintype "passive"))
      (node (ref "SJ6") (pin "2") (pinfunction "2_2") (pintype "passive"))
    )
    (net (code "20") (name "Net-(IC3-RX0)") (class "Default")
      (node (ref "C11") (pin "2") (pinfunction "2_2") (pintype "passive"))
      (node (ref "IC3") (pin "20") (pinfunction "RX0_20") (pintype "input"))
    )
    (net (code "21") (name "Net-(IC3-SCLK)") (class "Default")
      (node (ref "IC3") (pin "1") (pinfunction "SCLK_1") (pintype "output"))
      (node (ref "R4") (pin "1") (pinfunction "1_1") (pintype "passive"))
      (node (ref "SJ3") (pin "2") (pinfunction "2_2") (pintype "passive"))
    )
    (net (code "22") (name "Net-(IC3-SDIN{slash}HWMODE)") (class "Default")
      (node (ref "IC3") (pin "3") (pinfunction "SDIN/HWMODE_3") (pintype "output"))
      (node (ref "R3") (pin "1") (pinfunction "1_1") (pintype "passive"))
      (node (ref "SJ2") (pin "2") (pinfunction "2_2") (pintype "passive"))
    )
    (net (code "23") (name "Net-(IC3-SDOUT{slash}GPO2)") (class "Default")
      (node (ref "IC3") (pin "4") (pinfunction "SDOUT/GPO2_4") (pintype "output"))
      (node (ref "R2") (pin "1") (pinfunction "1_1") (pintype "passive"))
      (node (ref "SJ1") (pin "2") (pinfunction "2_2") (pintype "passive"))
    )
    (net (code "24") (name "Net-(IC3-XIN)") (class "Default")
      (node (ref "C12") (pin "2") (pinfunction "2_2") (pintype "passive"))
      (node (ref "IC3") (pin "11") (pinfunction "XIN_11") (pintype "bidirectional"))
      (node (ref "Q1") (pin "2") (pinfunction "2_2") (pintype "passive"))
    )
    (net (code "25") (name "Net-(IC3-XOP)") (class "Default")
      (node (ref "C13") (pin "2") (pinfunction "2_2") (pintype "passive"))
      (node (ref "IC3") (pin "10") (pinfunction "XOP_10") (pintype "bidirectional"))
      (node (ref "Q1") (pin "1") (pinfunction "1_1") (pintype "passive"))
    )
    (net (code "26") (name "Net-(IC4-CHSL)") (class "Default")
      (node (ref "IC4") (pin "2") (pinfunction "CHSL_2") (pintype "bidirectional"))
      (node (ref "R8") (pin "2") (pinfunction "2_2") (pintype "passive"))
      (node (ref "SJ9") (pin "2") (pinfunction "2_2") (pintype "passive"))
    )
    (net (code "27") (name "Net-(IC4-FMT0)") (class "Default")
      (node (ref "IC4") (pin "11") (pinfunction "FMT0_11") (pintype "input"))
      (node (ref "R26") (pin "2") (pinfunction "2_2") (pintype "passive"))
      (node (ref "SJ8") (pin "2") (pinfunction "2_2") (pintype "passive"))
    )
    (net (code "28") (name "Net-(IC4-FMT1)") (class "Default")
      (node (ref "IC4") (pin "12") (pinfunction "FMT1_12") (pintype "input"))
      (node (ref "R25") (pin "2") (pinfunction "2_2") (pintype "passive"))
      (node (ref "SJ7") (pin "2") (pinfunction "2_2") (pintype "passive"))
    )
    (net (code "29") (name "Net-(IC4-IREF)") (class "Default")
      (node (ref "IC4") (pin "20") (pinfunction "IREF_20") (pintype "input"))
      (node (ref "R10") (pin "1") (pinfunction "1_1") (pintype "passive"))
    )
    (net (code "30") (name "Net-(IC4-MONO)") (class "Default")
      (node (ref "IC4") (pin "1") (pinfunction "MONO_1") (pintype "bidirectional"))
      (node (ref "R27") (pin "2") (pinfunction "2_2") (pintype "passive"))
      (node (ref "SJ10") (pin "2") (pinfunction "2_2") (pintype "passive"))
    )
    (net (code "31") (name "Net-(IC4-VCOML)") (class "Default")
      (node (ref "C18") (pin "-") (pinfunction "-_-") (pintype "passive"))
      (node (ref "IC4") (pin "21") (pinfunction "VCOMR_21") (pintype "input"))
      (node (ref "IC4") (pin "22") (pinfunction "VCOML_22") (pintype "input"))
    )
    (net (code "32") (name "Net-(IC4-~{RST})") (class "Default")
      (node (ref "IC4") (pin "14") (pinfunction "~{RST}_14") (pintype "input"))
      (node (ref "R9") (pin "2") (pinfunction "2_2") (pintype "passive"))
    )
    (net (code "33") (name "Net-(IC5-CMP)") (class "Default")
      (node (ref "C32") (pin "2") (pinfunction "2_2") (pintype "passive"))
      (node (ref "IC5") (pin "5") (pinfunction "CMP_5") (pintype "passive"))
    )
    (net (code "34") (name "Net-(IC5-ON{slash}CMP)") (class "Default")
      (node (ref "C32") (pin "1") (pinfunction "1_1") (pintype "passive"))
      (node (ref "IC5") (pin "8") (pinfunction "ON/CMP_8") (pintype "passive"))
    )
    (net (code "35") (name "Net-(IC5-OUT)") (class "Default")
      (node (ref "C28") (pin "2") (pinfunction "2_2") (pintype "passive"))
      (node (ref "IC5") (pin "6") (pinfunction "OUT_6") (pintype "output"))
      (node (ref "R11") (pin "2") (pinfunction "2_2") (pintype "passive"))
      (node (ref "R15") (pin "1") (pinfunction "1_1") (pintype "passive"))
    )
    (net (code "36") (name "Net-(IC6-CMP)") (class "Default")
      (node (ref "C33") (pin "2") (pinfunction "2_2") (pintype "passive"))
      (node (ref "IC6") (pin "5") (pinfunction "CMP_5") (pintype "passive"))
    )
    (net (code "37") (name "Net-(IC6-ON{slash}CMP)") (class "Default")
      (node (ref "C33") (pin "1") (pinfunction "1_1") (pintype "passive"))
      (node (ref "IC6") (pin "8") (pinfunction "ON/CMP_8") (pintype "passive"))
    )
    (net (code "38") (name "Net-(IC6-OUT)") (class "Default")
      (node (ref "C29") (pin "2") (pinfunction "2_2") (pintype "passive"))
      (node (ref "IC6") (pin "6") (pinfunction "OUT_6") (pintype "output"))
      (node (ref "R12") (pin "2") (pinfunction "2_2") (pintype "passive"))
      (node (ref "R16") (pin "1") (pinfunction "1_1") (pintype "passive"))
    )
    (net (code "39") (name "Net-(IC7-CMP)") (class "Default")
      (node (ref "C34") (pin "2") (pinfunction "2_2") (pintype "passive"))
      (node (ref "IC7") (pin "5") (pinfunction "CMP_5") (pintype "passive"))
    )
    (net (code "40") (name "Net-(IC7-ON{slash}CMP)") (class "Default")
      (node (ref "C34") (pin "1") (pinfunction "1_1") (pintype "passive"))
      (node (ref "IC7") (pin "8") (pinfunction "ON/CMP_8") (pintype "passive"))
    )
    (net (code "41") (name "Net-(IC7-OUT)") (class "Default")
      (node (ref "C30") (pin "2") (pinfunction "2_2") (pintype "passive"))
      (node (ref "IC7") (pin "6") (pinfunction "OUT_6") (pintype "output"))
      (node (ref "R13") (pin "2") (pinfunction "2_2") (pintype "passive"))
      (node (ref "R17") (pin "1") (pinfunction "1_1") (pintype "passive"))
    )
    (net (code "42") (name "Net-(IC8-CMP)") (class "Default")
      (node (ref "C35") (pin "2") (pinfunction "2_2") (pintype "passive"))
      (node (ref "IC8") (pin "5") (pinfunction "CMP_5") (pintype "passive"))
    )
    (net (code "43") (name "Net-(IC8-ON{slash}CMP)") (class "Default")
      (node (ref "C35") (pin "1") (pinfunction "1_1") (pintype "passive"))
      (node (ref "IC8") (pin "8") (pinfunction "ON/CMP_8") (pintype "passive"))
    )
    (net (code "44") (name "Net-(IC9-+IN)") (class "Default")
      (node (ref "C37") (pin "2") (pinfunction "2_2") (pintype "passive"))
      (node (ref "C38") (pin "1") (pinfunction "1_1") (pintype "passive"))
      (node (ref "IC9") (pin "3") (pinfunction "+IN_3") (pintype "input"))
      (node (ref "R16") (pin "2") (pinfunction "2_2") (pintype "passive"))
      (node (ref "R20") (pin "2") (pinfunction "2_2") (pintype "passive"))
    )
    (net (code "45") (name "Net-(IC9--IN)") (class "Default")
      (node (ref "C36") (pin "2") (pinfunction "2_2") (pintype "passive"))
      (node (ref "C37") (pin "1") (pinfunction "1_1") (pintype "passive"))
      (node (ref "IC9") (pin "2") (pinfunction "-IN_2") (pintype "input"))
      (node (ref "R15") (pin "2") (pinfunction "2_2") (pintype "passive"))
      (node (ref "R19") (pin "1") (pinfunction "1_1") (pintype "passive"))
    )
    (net (code "46") (name "Net-(IC9-CMP)") (class "Default")
      (node (ref "C46") (pin "1") (pinfunction "1_1") (pintype "passive"))
      (node (ref "IC9") (pin "5") (pinfunction "CMP_5") (pintype "passive"))
    )
    (net (code "47") (name "Net-(IC9-ON{slash}CMP)") (class "Default")
      (node (ref "C46") (pin "2") (pinfunction "2_2") (pintype "passive"))
      (node (ref "IC9") (pin "8") (pinfunction "ON/CMP_8") (pintype "passive"))
    )
    (net (code "48") (name "Net-(IC9-OUT)") (class "Default")
      (node (ref "C36") (pin "1") (pinfunction "1_1") (pintype "passive"))
      (node (ref "IC9") (pin "6") (pinfunction "OUT_6") (pintype "output"))
      (node (ref "R19") (pin "2") (pinfunction "2_2") (pintype "passive"))
      (node (ref "R23") (pin "1") (pinfunction "1_1") (pintype "passive"))
    )
    (net (code "49") (name "Net-(IC10-+IN)") (class "Default")
      (node (ref "C40") (pin "2") (pinfunction "2_2") (pintype "passive"))
      (node (ref "C41") (pin "1") (pinfunction "1_1") (pintype "passive"))
      (node (ref "IC10") (pin "3") (pinfunction "+IN_3") (pintype "input"))
      (node (ref "R18") (pin "2") (pinfunction "2_2") (pintype "passive"))
      (node (ref "R22") (pin "2") (pinfunction "2_2") (pintype "passive"))
    )
    (net (code "50") (name "Net-(IC10--IN)") (class "Default")
      (node (ref "C39") (pin "2") (pinfunction "2_2") (pintype "passive"))
      (node (ref "C40") (pin "1") (pinfunction "1_1") (pintype "passive"))
      (node (ref "IC10") (pin "2") (pinfunction "-IN_2") (pintype "input"))
      (node (ref "R17") (pin "2") (pinfunction "2_2") (pintype "passive"))
      (node (ref "R21") (pin "1") (pinfunction "1_1") (pintype "passive"))
    )
    (net (code "51") (name "Net-(IC10-CMP)") (class "Default")
      (node (ref "C47") (pin "1") (pinfunction "1_1") (pintype "passive"))
      (node (ref "IC10") (pin "5") (pinfunction "CMP_5") (pintype "passive"))
    )
    (net (code "52") (name "Net-(IC10-ON{slash}CMP)") (class "Default")
      (node (ref "C47") (pin "2") (pinfunction "2_2") (pintype "passive"))
      (node (ref "IC10") (pin "8") (pinfunction "ON/CMP_8") (pintype "passive"))
    )
    (net (code "53") (name "Net-(IC10-OUT)") (class "Default")
      (node (ref "C39") (pin "1") (pinfunction "1_1") (pintype "passive"))
      (node (ref "IC10") (pin "6") (pinfunction "OUT_6") (pintype "output"))
      (node (ref "R21") (pin "2") (pinfunction "2_2") (pintype "passive"))
      (node (ref "R24") (pin "1") (pinfunction "1_1") (pintype "passive"))
    )
    (net (code "54") (name "VOUTR+") (class "Default")
      (node (ref "C31") (pin "2") (pinfunction "2_2") (pintype "passive"))
      (node (ref "IC8") (pin "6") (pinfunction "OUT_6") (pintype "output"))
      (node (ref "R14") (pin "2") (pinfunction "2_2") (pintype "passive"))
      (node (ref "R18") (pin "1") (pinfunction "1_1") (pintype "passive"))
    )
    (net (code "55") (name "unconnected-(BU2-Pad4)") (class "Default")
      (node (ref "BU2") (pin "4") (pinfunction "4_4") (pintype "passive"))
    )
    (net (code "56") (name "unconnected-(BU3-Pad4)") (class "Default")
      (node (ref "BU3") (pin "4") (pinfunction "4_4") (pintype "passive"))
    )
    (net (code "57") (name "unconnected-(IC3-CLKOUT-Pad9)") (class "Default")
      (node (ref "IC3") (pin "9") (pinfunction "CLKOUT_9") (pintype "bidirectional"))
    )
    (net (code "58") (name "unconnected-(IC3-DIN-Pad13)") (class "Default")
      (node (ref "IC3") (pin "13") (pinfunction "DIN_13") (pintype "input"))
    )
    (net (code "59") (name "unconnected-(IC3-TX0-Pad17)") (class "Default")
      (node (ref "IC3") (pin "17") (pinfunction "TX0_17") (pintype "output"))
    )
    (net (code "60") (name "unconnected-(IC4-ZERO-Pad13)") (class "Default")
      (node (ref "IC4") (pin "13") (pinfunction "ZERO_13") (pintype "bidirectional"))
    )
    (net (code "61") (name "unconnected-(IC5-ON-Pad1)") (class "Default")
      (node (ref "IC5") (pin "1") (pinfunction "ON_1") (pintype "passive"))
    )
    (net (code "62") (name "unconnected-(IC6-ON-Pad1)") (class "Default")
      (node (ref "IC6") (pin "1") (pinfunction "ON_1") (pintype "passive"))
    )
    (net (code "63") (name "unconnected-(IC7-ON-Pad1)") (class "Default")
      (node (ref "IC7") (pin "1") (pinfunction "ON_1") (pintype "passive"))
    )
    (net (code "64") (name "unconnected-(IC8-ON-Pad1)") (class "Default")
      (node (ref "IC8") (pin "1") (pinfunction "ON_1") (pintype "passive"))
    )
    (net (code "65") (name "unconnected-(IC9-ON-Pad1)") (class "Default")
      (node (ref "IC9") (pin "1") (pinfunction "ON_1") (pintype "passive"))
    )
    (net (code "66") (name "unconnected-(IC10-ON-Pad1)") (class "Default")
      (node (ref "IC10") (pin "1") (pinfunction "ON_1") (pintype "passive"))
    )
  )
)
